# ca_ca.net
KiCad netlist of a schematic drawn in EAGLE
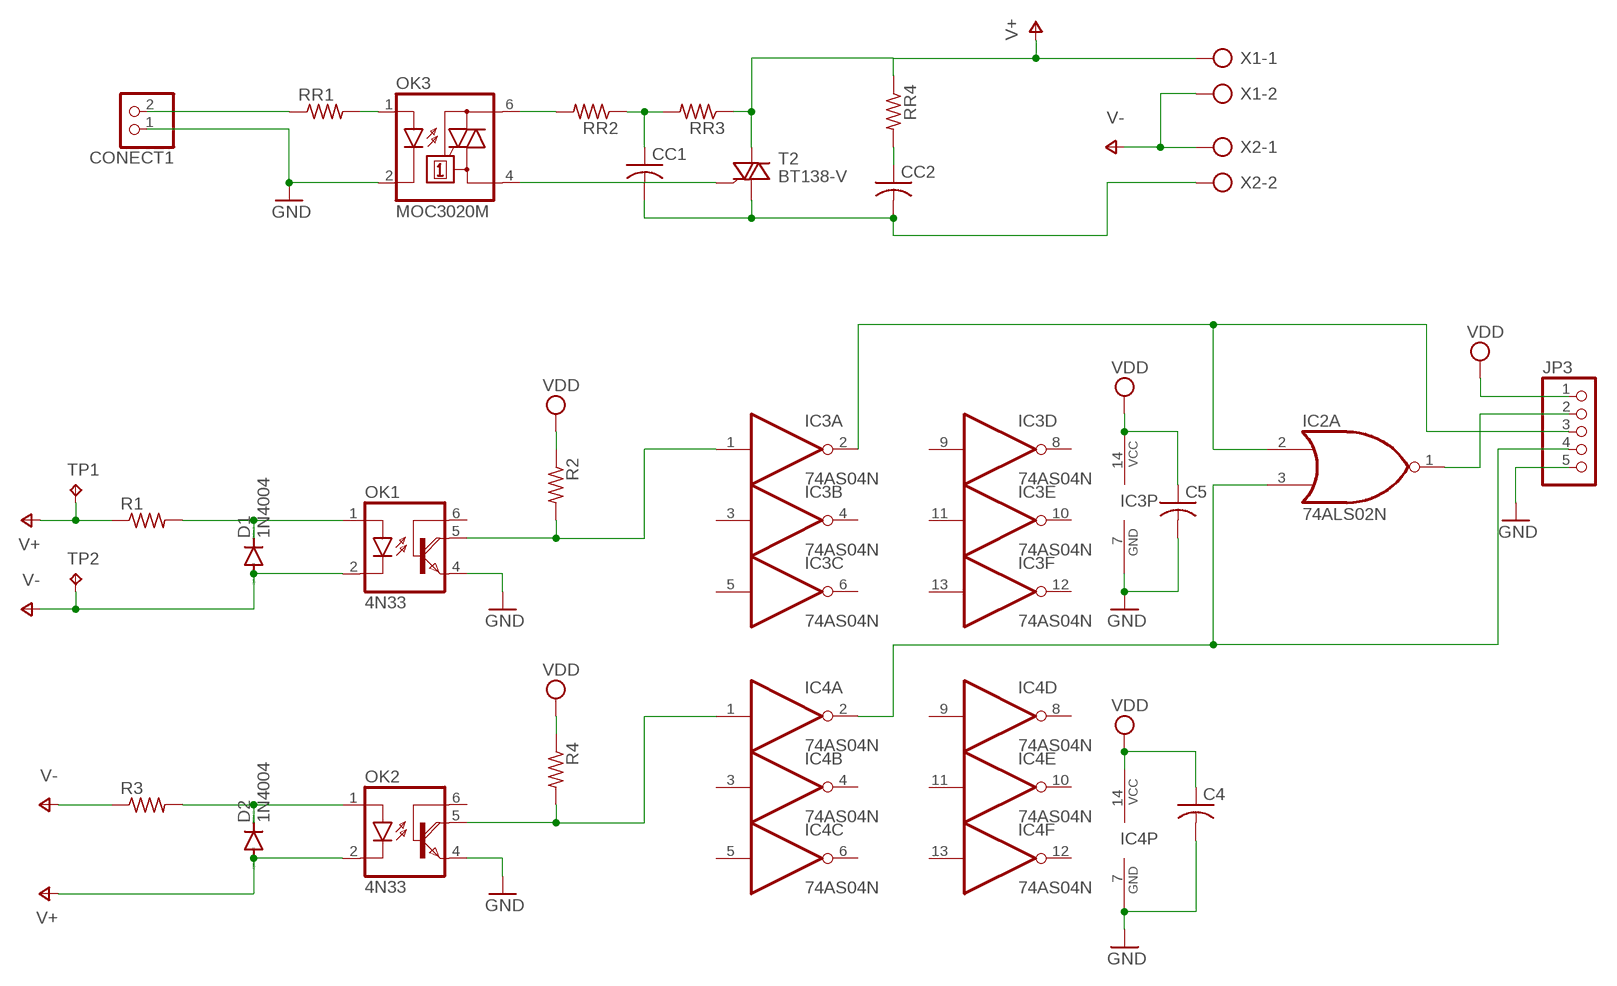
[diagram p0: schematic, sheet 1]

(export (version "E")
  (design (tool "Eeschema 10.0.6"))
  (components
    (comp (ref "C4")
      (value "C-US102-064X133")
      (footprint "eagle-import:C102-064X133")
      (libsource (lib "eagle-import") (part "C-US102-064X133"))
    )
    (comp (ref "C5")
      (value "C-US102-064X133")
      (footprint "eagle-import:C102-064X133")
      (libsource (lib "eagle-import") (part "C-US102-064X133"))
    )
    (comp (ref "CC1")
      (value "C-US102-064X133")
      (footprint "eagle-import:C102-064X133")
      (libsource (lib "eagle-import") (part "C-US102-064X133"))
    )
    (comp (ref "CC2")
      (value "C-US102-064X133")
      (footprint "eagle-import:C102-064X133")
      (libsource (lib "eagle-import") (part "C-US102-064X133"))
    )
    (comp (ref "CONECT1")
      (value "PINHD-1X2")
      (footprint "eagle-import:1X02")
      (libsource (lib "eagle-import") (part "PINHD-1X2"))
    )
    (comp (ref "D1")
      (value "1N4004")
      (footprint "eagle-import:DO41-10")
      (libsource (lib "eagle-import") (part "1N4004"))
    )
    (comp (ref "D2")
      (value "1N4004")
      (footprint "eagle-import:DO41-10")
      (libsource (lib "eagle-import") (part "1N4004"))
    )
    (comp (ref "IC2")
      (value "74ALS02N")
      (footprint "eagle-import:DIL14")
      (libsource (lib "eagle-import") (part "7402NALS"))
    )
    (comp (ref "IC3")
      (value "74AS04N")
      (footprint "eagle-import:DIL14")
      (libsource (lib "eagle-import") (part "7404NAS"))
    )
    (comp (ref "IC4")
      (value "74AS04N")
      (footprint "eagle-import:DIL14")
      (libsource (lib "eagle-import") (part "7404NAS"))
    )
    (comp (ref "JP3")
      (value "PINHD-1X5")
      (footprint "eagle-import:1X05")
      (libsource (lib "eagle-import") (part "PINHD-1X5"))
    )
    (comp (ref "OK1")
      (value "4N33")
      (footprint "eagle-import:DIL06")
      (fields (field (name "MF") "VISHAY/TELEFUNKEN"))
      (libsource (lib "eagle-import") (part "4N33"))
    )
    (comp (ref "OK2")
      (value "4N33")
      (footprint "eagle-import:DIL06")
      (fields (field (name "MF") "VISHAY/TELEFUNKEN"))
      (libsource (lib "eagle-import") (part "4N33"))
    )
    (comp (ref "OK3")
      (value "MOC3020M")
      (footprint "eagle-import:DIL06")
      (fields (field (name "MF") "FAIRCHILD SEMICONDUCTOR") (field (name "MPN") "MOC3020-M"))
      (libsource (lib "eagle-import") (part "MOC30M20"))
    )
    (comp (ref "R1")
      (value "R-US_0617/22")
      (footprint "eagle-import:0617_22")
      (libsource (lib "eagle-import") (part "R-US_0617/22"))
    )
    (comp (ref "R2")
      (value "R-US_0617/22")
      (footprint "eagle-import:0617_22")
      (libsource (lib "eagle-import") (part "R-US_0617/22"))
    )
    (comp (ref "R3")
      (value "R-US_0617/22")
      (footprint "eagle-import:0617_22")
      (libsource (lib "eagle-import") (part "R-US_0617/22"))
    )
    (comp (ref "R4")
      (value "R-US_0617/22")
      (footprint "eagle-import:0617_22")
      (libsource (lib "eagle-import") (part "R-US_0617/22"))
    )
    (comp (ref "RR1")
      (value "R-US_0617/22")
      (footprint "eagle-import:0617_22")
      (libsource (lib "eagle-import") (part "R-US_0617/22"))
    )
    (comp (ref "RR2")
      (value "R-US_0617/22")
      (footprint "eagle-import:0617_22")
      (libsource (lib "eagle-import") (part "R-US_0617/22"))
    )
    (comp (ref "RR3")
      (value "R-US_0617/22")
      (footprint "eagle-import:0617_22")
      (libsource (lib "eagle-import") (part "R-US_0617/22"))
    )
    (comp (ref "RR4")
      (value "R-US_0617/22")
      (footprint "eagle-import:0617_22")
      (libsource (lib "eagle-import") (part "R-US_0617/22"))
    )
    (comp (ref "T2")
      (value "BT138-V")
      (footprint "eagle-import:TO220BV")
      (libsource (lib "eagle-import") (part "BT138-V"))
    )
    (comp (ref "TP1")
      (value "TPPAD1-17Y")
      (footprint "eagle-import:P1-17Y")
      (libsource (lib "eagle-import") (part "TPPAD1-17Y"))
    )
    (comp (ref "TP2")
      (value "TPPAD1-17Y")
      (footprint "eagle-import:P1-17Y")
      (libsource (lib "eagle-import") (part "TPPAD1-17Y"))
    )
    (comp (ref "X1")
      (value "AK500/2-H")
      (footprint "eagle-import:AK500_2-H")
      (libsource (lib "eagle-import") (part "AK500/2-H"))
    )
    (comp (ref "X2")
      (value "AK500/2-H")
      (footprint "eagle-import:AK500_2-H")
      (libsource (lib "eagle-import") (part "AK500/2-H"))
    )
  )
  (nets
    (net (code "1") (name "GND") (class "Default")
      (node (ref "C4") (pin "2") (pinfunction "2_2") (pintype "passive"))
      (node (ref "C5") (pin "2") (pinfunction "2_2") (pintype "passive"))
      (node (ref "CONECT1") (pin "1") (pinfunction "1_1") (pintype "passive"))
      (node (ref "IC3") (pin "7") (pinfunction "GND_7") (pintype "power_in"))
      (node (ref "IC4") (pin "7") (pinfunction "GND_7") (pintype "power_in"))
      (node (ref "JP3") (pin "5") (pinfunction "5_5") (pintype "passive"))
      (node (ref "OK1") (pin "4") (pinfunction "E_4") (pintype "passive"))
      (node (ref "OK2") (pin "4") (pinfunction "E_4") (pintype "passive"))
      (node (ref "OK3") (pin "2") (pinfunction "C_2") (pintype "passive"))
    )
    (net (code "2") (name "Net-(CC1-Pad1)") (class "Default")
      (node (ref "CC1") (pin "1") (pinfunction "1_1") (pintype "passive"))
      (node (ref "RR2") (pin "1") (pinfunction "1_1") (pintype "passive"))
      (node (ref "RR3") (pin "2") (pinfunction "2_2") (pintype "passive"))
    )
    (net (code "3") (name "Net-(CC2-Pad1)") (class "Default")
      (node (ref "CC2") (pin "1") (pinfunction "1_1") (pintype "passive"))
      (node (ref "RR4") (pin "2") (pinfunction "2_2") (pintype "passive"))
    )
    (net (code "4") (name "Net-(CONECT1-Pad2)") (class "Default")
      (node (ref "CONECT1") (pin "2") (pinfunction "2_2") (pintype "passive"))
      (node (ref "RR1") (pin "1") (pinfunction "1_1") (pintype "passive"))
    )
    (net (code "5") (name "Net-(IC2A-I0)") (class "Default")
      (node (ref "IC2") (pin "2") (pinfunction "I0_2") (pintype "input"))
      (node (ref "IC3") (pin "2") (pinfunction "O_2") (pintype "output"))
      (node (ref "JP3") (pin "3") (pinfunction "3_3") (pintype "passive"))
    )
    (net (code "6") (name "Net-(IC2A-I1)") (class "Default")
      (node (ref "IC2") (pin "3") (pinfunction "I1_3") (pintype "input"))
      (node (ref "IC4") (pin "2") (pinfunction "O_2") (pintype "output"))
      (node (ref "JP3") (pin "4") (pinfunction "4_4") (pintype "passive"))
    )
    (net (code "7") (name "Net-(IC2A-O)") (class "Default")
      (node (ref "IC2") (pin "1") (pinfunction "O_1") (pintype "output"))
      (node (ref "JP3") (pin "2") (pinfunction "2_2") (pintype "passive"))
    )
    (net (code "8") (name "Net-(IC3A-I)") (class "Default")
      (node (ref "IC3") (pin "1") (pinfunction "I_1") (pintype "input"))
      (node (ref "OK1") (pin "5") (pinfunction "COL_5") (pintype "passive"))
      (node (ref "R2") (pin "2") (pinfunction "2_2") (pintype "passive"))
    )
    (net (code "9") (name "Net-(IC4A-I)") (class "Default")
      (node (ref "IC4") (pin "1") (pinfunction "I_1") (pintype "input"))
      (node (ref "OK2") (pin "5") (pinfunction "COL_5") (pintype "passive"))
      (node (ref "R4") (pin "2") (pinfunction "2_2") (pintype "passive"))
    )
    (net (code "10") (name "Net-(OK1-A)") (class "Default")
      (node (ref "D1") (pin "C") (pinfunction "C_C") (pintype "passive"))
      (node (ref "OK1") (pin "1") (pinfunction "A_1") (pintype "passive"))
      (node (ref "R1") (pin "2") (pinfunction "2_2") (pintype "passive"))
    )
    (net (code "11") (name "Net-(OK2-A)") (class "Default")
      (node (ref "D2") (pin "C") (pinfunction "C_C") (pintype "passive"))
      (node (ref "OK2") (pin "1") (pinfunction "A_1") (pintype "passive"))
      (node (ref "R3") (pin "2") (pinfunction "2_2") (pintype "passive"))
    )
    (net (code "12") (name "Net-(OK3-A)") (class "Default")
      (node (ref "OK3") (pin "1") (pinfunction "A_1") (pintype "passive"))
      (node (ref "RR1") (pin "2") (pinfunction "2_2") (pintype "passive"))
    )
    (net (code "13") (name "Net-(OK3-A1)") (class "Default")
      (node (ref "OK3") (pin "4") (pinfunction "A1_4") (pintype "passive"))
      (node (ref "T2") (pin "G") (pinfunction "G_G") (pintype "passive"))
    )
    (net (code "14") (name "Net-(OK3-A2)") (class "Default")
      (node (ref "OK3") (pin "6") (pinfunction "A2_6") (pintype "passive"))
      (node (ref "RR2") (pin "2") (pinfunction "2_2") (pintype "passive"))
    )
    (net (code "15") (name "Net-(T2-A1)") (class "Default")
      (node (ref "CC1") (pin "2") (pinfunction "2_2") (pintype "passive"))
      (node (ref "CC2") (pin "2") (pinfunction "2_2") (pintype "passive"))
      (node (ref "T2") (pin "T1") (pinfunction "A1_T1") (pintype "passive"))
      (node (ref "X2") (pin "2") (pinfunction "KL_2") (pintype "passive"))
    )
    (net (code "16") (name "V+") (class "Default")
      (node (ref "D2") (pin "A") (pinfunction "A_A") (pintype "passive"))
      (node (ref "OK2") (pin "2") (pinfunction "C_2") (pintype "passive"))
      (node (ref "R1") (pin "1") (pinfunction "1_1") (pintype "passive"))
      (node (ref "RR3") (pin "1") (pinfunction "1_1") (pintype "passive"))
      (node (ref "RR4") (pin "1") (pinfunction "1_1") (pintype "passive"))
      (node (ref "T2") (pin "T2") (pinfunction "A2_T2") (pintype "passive"))
      (node (ref "TP1") (pin "TP") (pinfunction "TP_TP") (pintype "input"))
      (node (ref "X1") (pin "1") (pinfunction "KL_1") (pintype "passive"))
    )
    (net (code "17") (name "V-") (class "Default")
      (node (ref "D1") (pin "A") (pinfunction "A_A") (pintype "passive"))
      (node (ref "OK1") (pin "2") (pinfunction "C_2") (pintype "passive"))
      (node (ref "R3") (pin "1") (pinfunction "1_1") (pintype "passive"))
      (node (ref "TP2") (pin "TP") (pinfunction "TP_TP") (pintype "input"))
      (node (ref "X1") (pin "2") (pinfunction "KL_2") (pintype "passive"))
      (node (ref "X2") (pin "1") (pinfunction "KL_1") (pintype "passive"))
    )
    (net (code "18") (name "VDD") (class "Default")
      (node (ref "C4") (pin "1") (pinfunction "1_1") (pintype "passive"))
      (node (ref "C5") (pin "1") (pinfunction "1_1") (pintype "passive"))
      (node (ref "IC3") (pin "14") (pinfunction "VCC_14") (pintype "power_in"))
      (node (ref "IC4") (pin "14") (pinfunction "VCC_14") (pintype "power_in"))
      (node (ref "JP3") (pin "1") (pinfunction "1_1") (pintype "passive"))
      (node (ref "R2") (pin "1") (pinfunction "1_1") (pintype "passive"))
      (node (ref "R4") (pin "1") (pinfunction "1_1") (pintype "passive"))
    )
    (net (code "19") (name "unconnected-(IC3B-I-Pad3)") (class "Default")
      (node (ref "IC3") (pin "3") (pinfunction "I_3") (pintype "input"))
    )
    (net (code "20") (name "unconnected-(IC3B-O-Pad4)") (class "Default")
      (node (ref "IC3") (pin "4") (pinfunction "O_4") (pintype "output"))
    )
    (net (code "21") (name "unconnected-(IC3C-I-Pad5)") (class "Default")
      (node (ref "IC3") (pin "5") (pinfunction "I_5") (pintype "input"))
    )
    (net (code "22") (name "unconnected-(IC3C-O-Pad6)") (class "Default")
      (node (ref "IC3") (pin "6") (pinfunction "O_6") (pintype "output"))
    )
    (net (code "23") (name "unconnected-(IC3D-I-Pad9)") (class "Default")
      (node (ref "IC3") (pin "9") (pinfunction "I_9") (pintype "input"))
    )
    (net (code "24") (name "unconnected-(IC3D-O-Pad8)") (class "Default")
      (node (ref "IC3") (pin "8") (pinfunction "O_8") (pintype "output"))
    )
    (net (code "25") (name "unconnected-(IC3E-I-Pad11)") (class "Default")
      (node (ref "IC3") (pin "11") (pinfunction "I_11") (pintype "input"))
    )
    (net (code "26") (name "unconnected-(IC3E-O-Pad10)") (class "Default")
      (node (ref "IC3") (pin "10") (pinfunction "O_10") (pintype "output"))
    )
    (net (code "27") (name "unconnected-(IC3F-I-Pad13)") (class "Default")
      (node (ref "IC3") (pin "13") (pinfunction "I_13") (pintype "input"))
    )
    (net (code "28") (name "unconnected-(IC3F-O-Pad12)") (class "Default")
      (node (ref "IC3") (pin "12") (pinfunction "O_12") (pintype "output"))
    )
    (net (code "29") (name "unconnected-(IC4B-I-Pad3)") (class "Default")
      (node (ref "IC4") (pin "3") (pinfunction "I_3") (pintype "input"))
    )
    (net (code "30") (name "unconnected-(IC4B-O-Pad4)") (class "Default")
      (node (ref "IC4") (pin "4") (pinfunction "O_4") (pintype "output"))
    )
    (net (code "31") (name "unconnected-(IC4C-I-Pad5)") (class "Default")
      (node (ref "IC4") (pin "5") (pinfunction "I_5") (pintype "input"))
    )
    (net (code "32") (name "unconnected-(IC4C-O-Pad6)") (class "Default")
      (node (ref "IC4") (pin "6") (pinfunction "O_6") (pintype "output"))
    )
    (net (code "33") (name "unconnected-(IC4D-I-Pad9)") (class "Default")
      (node (ref "IC4") (pin "9") (pinfunction "I_9") (pintype "input"))
    )
    (net (code "34") (name "unconnected-(IC4D-O-Pad8)") (class "Default")
      (node (ref "IC4") (pin "8") (pinfunction "O_8") (pintype "output"))
    )
    (net (code "35") (name "unconnected-(IC4E-I-Pad11)") (class "Default")
      (node (ref "IC4") (pin "11") (pinfunction "I_11") (pintype "input"))
    )
    (net (code "36") (name "unconnected-(IC4E-O-Pad10)") (class "Default")
      (node (ref "IC4") (pin "10") (pinfunction "O_10") (pintype "output"))
    )
    (net (code "37") (name "unconnected-(IC4F-I-Pad13)") (class "Default")
      (node (ref "IC4") (pin "13") (pinfunction "I_13") (pintype "input"))
    )
    (net (code "38") (name "unconnected-(IC4F-O-Pad12)") (class "Default")
      (node (ref "IC4") (pin "12") (pinfunction "O_12") (pintype "output"))
    )
    (net (code "39") (name "unconnected-(OK1-B-Pad6)") (class "Default")
      (node (ref "OK1") (pin "6") (pinfunction "B_6") (pintype "passive"))
    )
    (net (code "40") (name "unconnected-(OK2-B-Pad6)") (class "Default")
      (node (ref "OK2") (pin "6") (pinfunction "B_6") (pintype "passive"))
    )
  )
)
